# Sheet1.net
KiCad netlist of a schematic drawn in Altium Designer
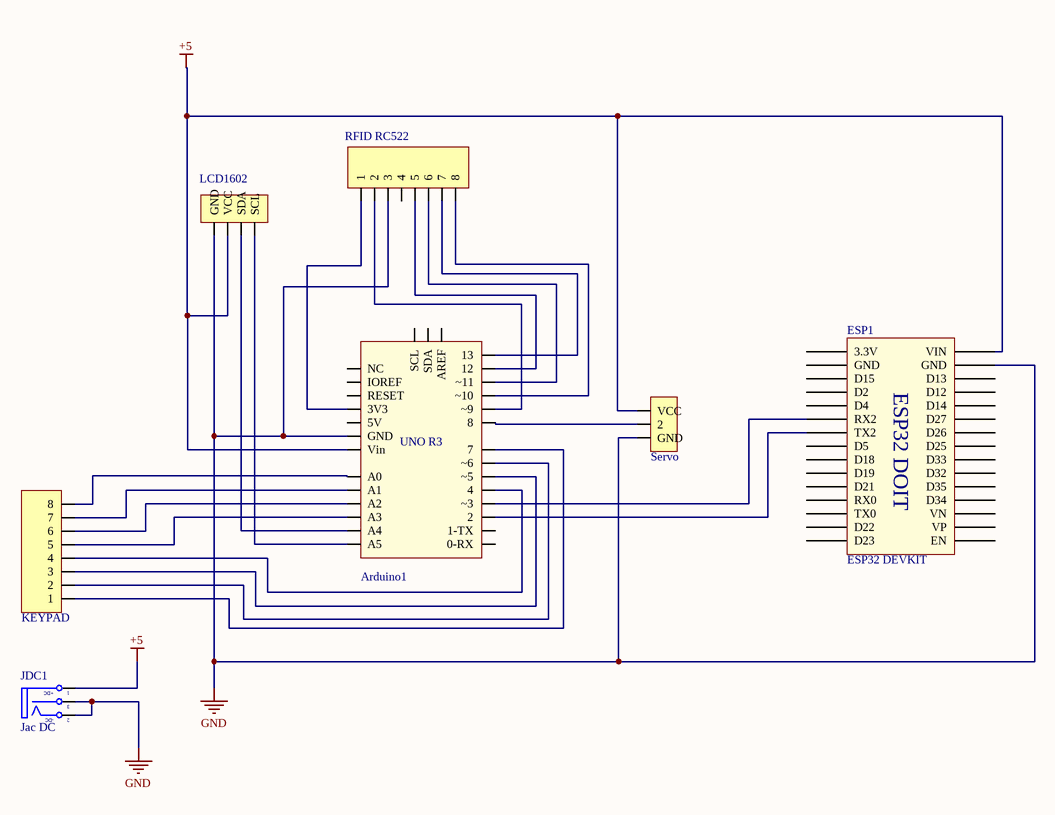
[diagram p0: Sheet1.SchDoc]

(export (version "E")
  (design (tool "Eeschema 10.0.6"))
  (components
    (comp (ref "Arduino1")
      (value "Arduino Uno R3")
      (footprint "Arduino UNO R3")
      (description "Arduino UNO R3")
      (libsource (lib "LIBRARY") (part "Arduino Uno R3"))
    )
    (comp (ref "ESP1")
      (value "ESP32 DEVKIT")
      (footprint "ESP32 WROOM 32 KIT")
      (libsource (lib "Module") (part "ESP32 WROOM 32 KIT"))
    )
    (comp (ref "JDC1")
      (value "Jac DC")
      (footprint "DC-IN")
      (description "Jac DC input")
      (libsource (lib "Thuvien3D") (part "DCIN"))
    )
    (comp (ref "JP1")
      (value "RFID RC522")
      (footprint "JP 1x8 CC")
      (description "Cắm")
      (libsource (lib "Jump") (part "JP 1x8 2.54 Cai Cong"))
    )
    (comp (ref "JP2")
      (value "LCD1602")
      (footprint "JP 1x4 CC")
      (description "Cắm")
      (libsource (lib "Jump") (part "JP 1x4 2.54 Cai Cong"))
    )
    (comp (ref "JP3")
      (value "Servo")
      (footprint "JP 1x3 DC")
      (description "Cắm")
      (libsource (lib "Jump") (part "JP 1x3 2.54 Duc Cong"))
    )
    (comp (ref "JP4")
      (value "KEYPAD")
      (footprint "JP 1x8 DC")
      (description "Cắm")
      (libsource (lib "Jump") (part "JP 1x8 2.54 Duc Cong"))
    )
  )
  (nets
    (net (code "1") (name "+5") (class "Default")
      (node (ref "Arduino1") (pin "Vin") (pinfunction "Vin_Vin") (pintype "passive"))
      (node (ref "ESP1") (pin "15") (pinfunction "VIN_15") (pintype "passive"))
      (node (ref "JDC1") (pin "1") (pinfunction "T_1") (pintype "passive"))
      (node (ref "JP2") (pin "2") (pinfunction "VCC_2") (pintype "passive"))
      (node (ref "JP3") (pin "1") (pinfunction "VCC_1") (pintype "passive"))
    )
    (net (code "2") (name "GND") (class "Default")
      (node (ref "Arduino1") (pin "GND") (pinfunction "GND_GND") (pintype "passive"))
      (node (ref "ESP1") (pin "14") (pinfunction "GND_14") (pintype "passive"))
      (node (ref "JDC1") (pin "2") (pinfunction "TN_2") (pintype "passive"))
      (node (ref "JDC1") (pin "3") (pinfunction "S_3") (pintype "power_in"))
      (node (ref "JP1") (pin "3") (pinfunction "3_3") (pintype "passive"))
      (node (ref "JP2") (pin "1") (pinfunction "GND_1") (pintype "passive"))
      (node (ref "JP3") (pin "3") (pinfunction "GND_3") (pintype "passive"))
    )
    (net (code "3") (name "Net-(Arduino1-Pad3V3)") (class "Default")
      (node (ref "Arduino1") (pin "3V3") (pinfunction "3V3_3V3") (pintype "passive"))
      (node (ref "JP1") (pin "1") (pinfunction "1_1") (pintype "passive"))
    )
    (net (code "4") (name "Net-(Arduino1-Pad4)") (class "Default")
      (node (ref "Arduino1") (pin "4") (pinfunction "4_4") (pintype "passive"))
      (node (ref "JP4") (pin "4") (pinfunction "4_4") (pintype "passive"))
    )
    (net (code "5") (name "Net-(Arduino1-Pad7)") (class "Default")
      (node (ref "Arduino1") (pin "7") (pinfunction "7_7") (pintype "passive"))
      (node (ref "JP4") (pin "1") (pinfunction "1_1") (pintype "passive"))
    )
    (net (code "6") (name "Net-(Arduino1-Pad8)") (class "Default")
      (node (ref "Arduino1") (pin "8") (pinfunction "8_8") (pintype "passive"))
      (node (ref "JP3") (pin "2") (pinfunction "2_2") (pintype "passive"))
    )
    (net (code "7") (name "Net-(Arduino1-Pad12)") (class "Default")
      (node (ref "Arduino1") (pin "12") (pinfunction "12_12") (pintype "passive"))
      (node (ref "JP1") (pin "5") (pinfunction "5_5") (pintype "passive"))
    )
    (net (code "8") (name "Net-(Arduino1-Pad13)") (class "Default")
      (node (ref "Arduino1") (pin "13") (pinfunction "13_13") (pintype "passive"))
      (node (ref "JP1") (pin "7") (pinfunction "7_7") (pintype "passive"))
    )
    (net (code "9") (name "Net-(Arduino1-PadA0)") (class "Default")
      (node (ref "Arduino1") (pin "A0") (pinfunction "A0_A0") (pintype "passive"))
      (node (ref "JP4") (pin "8") (pinfunction "8_8") (pintype "passive"))
    )
    (net (code "10") (name "Net-(Arduino1-PadA1)") (class "Default")
      (node (ref "Arduino1") (pin "A1") (pinfunction "A1_A1") (pintype "passive"))
      (node (ref "JP4") (pin "7") (pinfunction "7_7") (pintype "passive"))
    )
    (net (code "11") (name "Net-(Arduino1-PadA2)") (class "Default")
      (node (ref "Arduino1") (pin "A2") (pinfunction "A2_A2") (pintype "passive"))
      (node (ref "JP4") (pin "6") (pinfunction "6_6") (pintype "passive"))
    )
    (net (code "12") (name "Net-(Arduino1-PadA3)") (class "Default")
      (node (ref "Arduino1") (pin "A3") (pinfunction "A3_A3") (pintype "passive"))
      (node (ref "JP4") (pin "5") (pinfunction "5_5") (pintype "passive"))
    )
    (net (code "13") (name "Net-(Arduino1-Pad~5)") (class "Default")
      (node (ref "Arduino1") (pin "~5") (pinfunction "~5_~5") (pintype "passive"))
      (node (ref "JP4") (pin "3") (pinfunction "3_3") (pintype "passive"))
    )
    (net (code "14") (name "Net-(Arduino1-Pad~6)") (class "Default")
      (node (ref "Arduino1") (pin "~6") (pinfunction "~6_~6") (pintype "passive"))
      (node (ref "JP4") (pin "2") (pinfunction "2_2") (pintype "passive"))
    )
    (net (code "15") (name "Net-(Arduino1-Pad~9)") (class "Default")
      (node (ref "Arduino1") (pin "~9") (pinfunction "~9_~9") (pintype "passive"))
      (node (ref "JP1") (pin "2") (pinfunction "2_2") (pintype "passive"))
    )
    (net (code "16") (name "Net-(Arduino1-Pad~10)") (class "Default")
      (node (ref "Arduino1") (pin "~10") (pinfunction "~10_~10") (pintype "passive"))
      (node (ref "JP1") (pin "8") (pinfunction "8_8") (pintype "passive"))
    )
    (net (code "17") (name "Net-(Arduino1-Pad~11)") (class "Default")
      (node (ref "Arduino1") (pin "~11") (pinfunction "~11_~11") (pintype "passive"))
      (node (ref "JP1") (pin "6") (pinfunction "6_6") (pintype "passive"))
    )
    (net (code "18") (name "Net-(ESP1-RX2)") (class "Default")
      (node (ref "Arduino1") (pin "~3") (pinfunction "~3_~3") (pintype "passive"))
      (node (ref "ESP1") (pin "21") (pinfunction "RX2_21") (pintype "passive"))
    )
    (net (code "19") (name "Net-(ESP1-TX2)") (class "Default")
      (node (ref "Arduino1") (pin "2") (pinfunction "2_2") (pintype "passive"))
      (node (ref "ESP1") (pin "22") (pinfunction "TX2_22") (pintype "passive"))
    )
    (net (code "20") (name "Net-(JP2-SCL)") (class "Default")
      (node (ref "Arduino1") (pin "A5") (pinfunction "A5_A5") (pintype "passive"))
      (node (ref "JP2") (pin "4") (pinfunction "SCL_4") (pintype "passive"))
    )
    (net (code "21") (name "Net-(JP2-SDA)") (class "Default")
      (node (ref "Arduino1") (pin "A4") (pinfunction "A4_A4") (pintype "passive"))
      (node (ref "JP2") (pin "3") (pinfunction "SDA_3") (pintype "passive"))
    )
    (net (code "22") (name "unconnected-(Arduino1-Pad0-RX)") (class "Default")
      (node (ref "Arduino1") (pin "0-RX") (pinfunction "0-RX_0-RX") (pintype "passive"))
    )
    (net (code "23") (name "unconnected-(Arduino1-Pad1-TX)") (class "Default")
      (node (ref "Arduino1") (pin "1-TX") (pinfunction "1-TX_1-TX") (pintype "passive"))
    )
    (net (code "24") (name "unconnected-(Arduino1-Pad5V)") (class "Default")
      (node (ref "Arduino1") (pin "5V") (pinfunction "5V_5V") (pintype "passive"))
    )
    (net (code "25") (name "unconnected-(Arduino1-PadAREF)") (class "Default")
      (node (ref "Arduino1") (pin "AREF") (pinfunction "AREF_AREF") (pintype "passive"))
    )
    (net (code "26") (name "unconnected-(Arduino1-PadIOREF)") (class "Default")
      (node (ref "Arduino1") (pin "IOREF") (pinfunction "IOREF_IOREF") (pintype "passive"))
    )
    (net (code "27") (name "unconnected-(Arduino1-PadNC)") (class "Default")
      (node (ref "Arduino1") (pin "NC") (pinfunction "NC_NC") (pintype "passive"))
    )
    (net (code "28") (name "unconnected-(Arduino1-PadRESET)") (class "Default")
      (node (ref "Arduino1") (pin "RESET") (pinfunction "RESET_RESET") (pintype "passive"))
    )
    (net (code "29") (name "unconnected-(Arduino1-PadSCL)") (class "Default")
      (node (ref "Arduino1") (pin "SCL") (pinfunction "SCL_SCL") (pintype "passive"))
    )
    (net (code "30") (name "unconnected-(Arduino1-PadSDA)") (class "Default")
      (node (ref "Arduino1") (pin "SDA") (pinfunction "SDA_SDA") (pintype "passive"))
    )
    (net (code "31") (name "unconnected-(ESP1-3.3V-Pad16)") (class "Default")
      (node (ref "ESP1") (pin "16") (pinfunction "3.3V_16") (pintype "passive"))
    )
    (net (code "32") (name "unconnected-(ESP1-D2-Pad19)") (class "Default")
      (node (ref "ESP1") (pin "19") (pinfunction "D2_19") (pintype "passive"))
    )
    (net (code "33") (name "unconnected-(ESP1-D4-Pad20)") (class "Default")
      (node (ref "ESP1") (pin "20") (pinfunction "D4_20") (pintype "passive"))
    )
    (net (code "34") (name "unconnected-(ESP1-D5-Pad23)") (class "Default")
      (node (ref "ESP1") (pin "23") (pinfunction "D5_23") (pintype "passive"))
    )
    (net (code "35") (name "unconnected-(ESP1-D12-Pad12)") (class "Default")
      (node (ref "ESP1") (pin "12") (pinfunction "D12_12") (pintype "passive"))
    )
    (net (code "36") (name "unconnected-(ESP1-D13-Pad13)") (class "Default")
      (node (ref "ESP1") (pin "13") (pinfunction "D13_13") (pintype "passive"))
    )
    (net (code "37") (name "unconnected-(ESP1-D14-Pad11)") (class "Default")
      (node (ref "ESP1") (pin "11") (pinfunction "D14_11") (pintype "passive"))
    )
    (net (code "38") (name "unconnected-(ESP1-D15-Pad18)") (class "Default")
      (node (ref "ESP1") (pin "18") (pinfunction "D15_18") (pintype "passive"))
    )
    (net (code "39") (name "unconnected-(ESP1-D18-Pad24)") (class "Default")
      (node (ref "ESP1") (pin "24") (pinfunction "D18_24") (pintype "passive"))
    )
    (net (code "40") (name "unconnected-(ESP1-D19-Pad25)") (class "Default")
      (node (ref "ESP1") (pin "25") (pinfunction "D19_25") (pintype "passive"))
    )
    (net (code "41") (name "unconnected-(ESP1-D21-Pad26)") (class "Default")
      (node (ref "ESP1") (pin "26") (pinfunction "D21_26") (pintype "passive"))
    )
    (net (code "42") (name "unconnected-(ESP1-D22-Pad29)") (class "Default")
      (node (ref "ESP1") (pin "29") (pinfunction "D22_29") (pintype "passive"))
    )
    (net (code "43") (name "unconnected-(ESP1-D23-Pad30)") (class "Default")
      (node (ref "ESP1") (pin "30") (pinfunction "D23_30") (pintype "passive"))
    )
    (net (code "44") (name "unconnected-(ESP1-D25-Pad8)") (class "Default")
      (node (ref "ESP1") (pin "8") (pinfunction "D25_8") (pintype "passive"))
    )
    (net (code "45") (name "unconnected-(ESP1-D26-Pad9)") (class "Default")
      (node (ref "ESP1") (pin "9") (pinfunction "D26_9") (pintype "passive"))
    )
    (net (code "46") (name "unconnected-(ESP1-D27-Pad10)") (class "Default")
      (node (ref "ESP1") (pin "10") (pinfunction "D27_10") (pintype "passive"))
    )
    (net (code "47") (name "unconnected-(ESP1-D32-Pad6)") (class "Default")
      (node (ref "ESP1") (pin "6") (pinfunction "D32_6") (pintype "passive"))
    )
    (net (code "48") (name "unconnected-(ESP1-D33-Pad7)") (class "Default")
      (node (ref "ESP1") (pin "7") (pinfunction "D33_7") (pintype "passive"))
    )
    (net (code "49") (name "unconnected-(ESP1-D34-Pad4)") (class "Default")
      (node (ref "ESP1") (pin "4") (pinfunction "D34_4") (pintype "passive"))
    )
    (net (code "50") (name "unconnected-(ESP1-D35-Pad5)") (class "Default")
      (node (ref "ESP1") (pin "5") (pinfunction "D35_5") (pintype "passive"))
    )
    (net (code "51") (name "unconnected-(ESP1-EN-Pad1)") (class "Default")
      (node (ref "ESP1") (pin "1") (pinfunction "EN_1") (pintype "passive"))
    )
    (net (code "52") (name "unconnected-(ESP1-GND-Pad17)") (class "Default")
      (node (ref "ESP1") (pin "17") (pinfunction "GND_17") (pintype "passive"))
    )
    (net (code "53") (name "unconnected-(ESP1-RX0-Pad27)") (class "Default")
      (node (ref "ESP1") (pin "27") (pinfunction "RX0_27") (pintype "passive"))
    )
    (net (code "54") (name "unconnected-(ESP1-TX0-Pad28)") (class "Default")
      (node (ref "ESP1") (pin "28") (pinfunction "TX0_28") (pintype "passive"))
    )
    (net (code "55") (name "unconnected-(ESP1-VN-Pad3)") (class "Default")
      (node (ref "ESP1") (pin "3") (pinfunction "VN_3") (pintype "passive"))
    )
    (net (code "56") (name "unconnected-(ESP1-VP-Pad2)") (class "Default")
      (node (ref "ESP1") (pin "2") (pinfunction "VP_2") (pintype "passive"))
    )
    (net (code "57") (name "unconnected-(JP1-Pad4)") (class "Default")
      (node (ref "JP1") (pin "4") (pinfunction "4_4") (pintype "passive"))
    )
  )
)
